# Activities.net
KiCad netlist of a schematic drawn in EAGLE
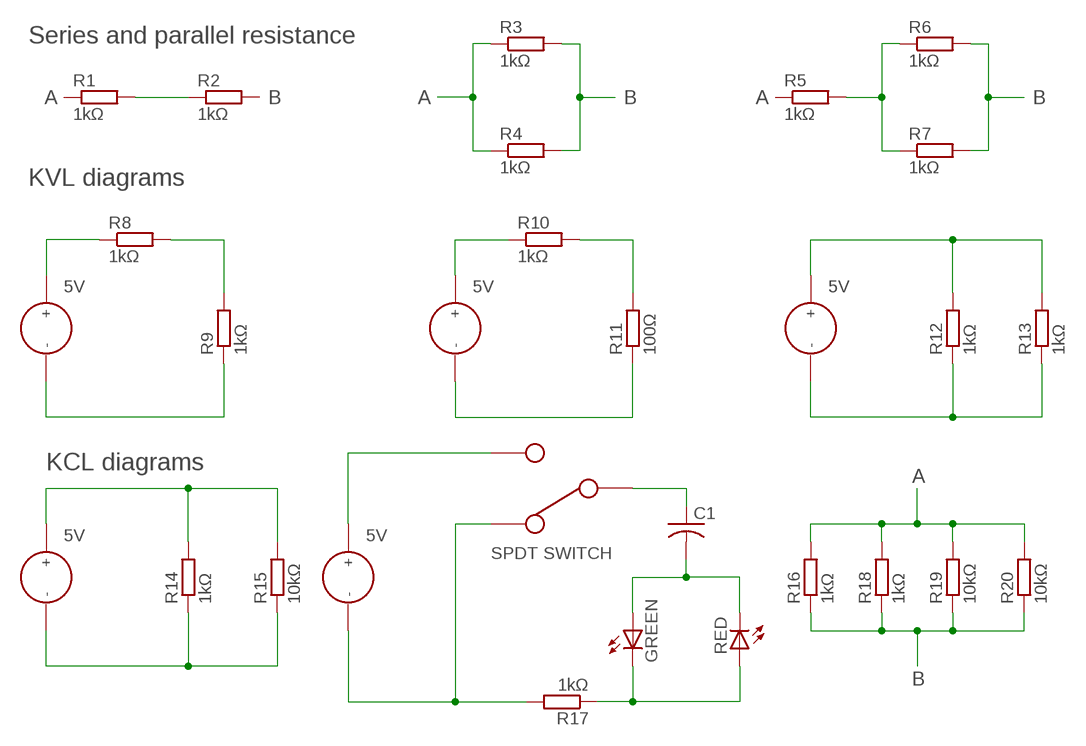
[diagram p0: schematic, sheet 1]

(export (version "E")
  (design (tool "Eeschema 10.0.6"))
  (components
    (comp (ref "C1")
      (value "C-US025-025X050")
      (footprint "eagle-import:C025-025X050")
      (libsource (lib "eagle-import") (part "C-US025-025X050"))
    )
    (comp (ref "GREEN")
      (value "LED3MM")
      (footprint "eagle-import:LED3MM")
      (libsource (lib "eagle-import") (part "LED3MM"))
    )
    (comp (ref "R1")
      (value "1kΩ")
      (footprint "eagle-import:0207_10")
      (libsource (lib "eagle-import") (part "R-EU_0207/10"))
    )
    (comp (ref "R2")
      (value "1kΩ")
      (footprint "eagle-import:0207_10")
      (libsource (lib "eagle-import") (part "R-EU_0207/10"))
    )
    (comp (ref "R3")
      (value "1kΩ")
      (footprint "eagle-import:0207_10")
      (libsource (lib "eagle-import") (part "R-EU_0207/10"))
    )
    (comp (ref "R4")
      (value "1kΩ")
      (footprint "eagle-import:0207_10")
      (libsource (lib "eagle-import") (part "R-EU_0207/10"))
    )
    (comp (ref "R5")
      (value "1kΩ")
      (footprint "eagle-import:0207_10")
      (libsource (lib "eagle-import") (part "R-EU_0207/10"))
    )
    (comp (ref "R6")
      (value "1kΩ")
      (footprint "eagle-import:0207_10")
      (libsource (lib "eagle-import") (part "R-EU_0207/10"))
    )
    (comp (ref "R7")
      (value "1kΩ")
      (footprint "eagle-import:0207_10")
      (libsource (lib "eagle-import") (part "R-EU_0207/10"))
    )
    (comp (ref "R8")
      (value "1kΩ")
      (footprint "eagle-import:0207_10")
      (libsource (lib "eagle-import") (part "R-EU_0207/10"))
    )
    (comp (ref "R9")
      (value "1kΩ")
      (footprint "eagle-import:0207_10")
      (libsource (lib "eagle-import") (part "R-EU_0207/10"))
    )
    (comp (ref "R10")
      (value "1kΩ")
      (footprint "eagle-import:0207_10")
      (libsource (lib "eagle-import") (part "R-EU_0207/10"))
    )
    (comp (ref "R11")
      (value "100Ω")
      (footprint "eagle-import:0207_10")
      (libsource (lib "eagle-import") (part "R-EU_0207/10"))
    )
    (comp (ref "R12")
      (value "1kΩ")
      (footprint "eagle-import:0207_10")
      (libsource (lib "eagle-import") (part "R-EU_0207/10"))
    )
    (comp (ref "R13")
      (value "1kΩ")
      (footprint "eagle-import:0207_10")
      (libsource (lib "eagle-import") (part "R-EU_0207/10"))
    )
    (comp (ref "R14")
      (value "1kΩ")
      (footprint "eagle-import:0207_10")
      (libsource (lib "eagle-import") (part "R-EU_0207/10"))
    )
    (comp (ref "R15")
      (value "10kΩ")
      (footprint "eagle-import:0207_10")
      (libsource (lib "eagle-import") (part "R-EU_0207/10"))
    )
    (comp (ref "R16")
      (value "1kΩ")
      (footprint "eagle-import:0207_10")
      (libsource (lib "eagle-import") (part "R-EU_0207/10"))
    )
    (comp (ref "R17")
      (value "1kΩ")
      (footprint "eagle-import:0207_10")
      (libsource (lib "eagle-import") (part "R-EU_0207/10"))
    )
    (comp (ref "R18")
      (value "1kΩ")
      (footprint "eagle-import:0207_10")
      (libsource (lib "eagle-import") (part "R-EU_0207/10"))
    )
    (comp (ref "R19")
      (value "10kΩ")
      (footprint "eagle-import:0207_10")
      (libsource (lib "eagle-import") (part "R-EU_0207/10"))
    )
    (comp (ref "R20")
      (value "10kΩ")
      (footprint "eagle-import:0207_10")
      (libsource (lib "eagle-import") (part "R-EU_0207/10"))
    )
    (comp (ref "RED")
      (value "LED3MM")
      (footprint "eagle-import:LED3MM")
      (libsource (lib "eagle-import") (part "LED3MM"))
    )
    (comp (ref "U$1")
      (value "SPDT")
      (footprint "eagle-import:SPDT")
      (libsource (lib "eagle-import") (part "SPDT"))
    )
    (comp (ref "V1")
      (value "5V")
      (footprint "eagle-import:VOLTAGE_SOURCE")
      (libsource (lib "eagle-import") (part "VOLTAGE_SOURCE"))
    )
    (comp (ref "V2")
      (value "5V")
      (footprint "eagle-import:VOLTAGE_SOURCE")
      (libsource (lib "eagle-import") (part "VOLTAGE_SOURCE"))
    )
    (comp (ref "V3")
      (value "5V")
      (footprint "eagle-import:VOLTAGE_SOURCE")
      (libsource (lib "eagle-import") (part "VOLTAGE_SOURCE"))
    )
    (comp (ref "V7")
      (value "5V")
      (footprint "eagle-import:VOLTAGE_SOURCE")
      (libsource (lib "eagle-import") (part "VOLTAGE_SOURCE"))
    )
    (comp (ref "V8")
      (value "5V")
      (footprint "eagle-import:VOLTAGE_SOURCE")
      (libsource (lib "eagle-import") (part "VOLTAGE_SOURCE"))
    )
  )
  (nets
    (net (code "1") (name "Net-(GREEN-C)") (class "Default")
      (node (ref "GREEN") (pin "K") (pinfunction "C_K") (pintype "passive"))
      (node (ref "R17") (pin "1") (pinfunction "1_1") (pintype "passive"))
      (node (ref "RED") (pin "A") (pinfunction "A_A") (pintype "passive"))
    )
    (net (code "2") (name "Net-(R1-Pad2)") (class "Default")
      (node (ref "R1") (pin "2") (pinfunction "2_2") (pintype "passive"))
      (node (ref "R2") (pin "1") (pinfunction "1_1") (pintype "passive"))
    )
    (net (code "3") (name "Net-(R3-Pad1)") (class "Default")
      (node (ref "R3") (pin "1") (pinfunction "1_1") (pintype "passive"))
      (node (ref "R4") (pin "1") (pinfunction "1_1") (pintype "passive"))
    )
    (net (code "4") (name "Net-(R3-Pad2)") (class "Default")
      (node (ref "R3") (pin "2") (pinfunction "2_2") (pintype "passive"))
      (node (ref "R4") (pin "2") (pinfunction "2_2") (pintype "passive"))
    )
    (net (code "5") (name "Net-(R5-Pad2)") (class "Default")
      (node (ref "R5") (pin "2") (pinfunction "2_2") (pintype "passive"))
      (node (ref "R6") (pin "1") (pinfunction "1_1") (pintype "passive"))
      (node (ref "R7") (pin "1") (pinfunction "1_1") (pintype "passive"))
    )
    (net (code "6") (name "Net-(R6-Pad2)") (class "Default")
      (node (ref "R6") (pin "2") (pinfunction "2_2") (pintype "passive"))
      (node (ref "R7") (pin "2") (pinfunction "2_2") (pintype "passive"))
    )
    (net (code "7") (name "Net-(R8-Pad2)") (class "Default")
      (node (ref "R8") (pin "2") (pinfunction "2_2") (pintype "passive"))
      (node (ref "R9") (pin "2") (pinfunction "2_2") (pintype "passive"))
    )
    (net (code "8") (name "Net-(R10-Pad2)") (class "Default")
      (node (ref "R10") (pin "2") (pinfunction "2_2") (pintype "passive"))
      (node (ref "R11") (pin "2") (pinfunction "2_2") (pintype "passive"))
    )
    (net (code "9") (name "Net-(R16-Pad1)") (class "Default")
      (node (ref "R16") (pin "1") (pinfunction "1_1") (pintype "passive"))
      (node (ref "R18") (pin "1") (pinfunction "1_1") (pintype "passive"))
      (node (ref "R19") (pin "1") (pinfunction "1_1") (pintype "passive"))
      (node (ref "R20") (pin "1") (pinfunction "1_1") (pintype "passive"))
    )
    (net (code "10") (name "Net-(R16-Pad2)") (class "Default")
      (node (ref "R16") (pin "2") (pinfunction "2_2") (pintype "passive"))
      (node (ref "R18") (pin "2") (pinfunction "2_2") (pintype "passive"))
      (node (ref "R19") (pin "2") (pinfunction "2_2") (pintype "passive"))
      (node (ref "R20") (pin "2") (pinfunction "2_2") (pintype "passive"))
    )
    (net (code "11") (name "Net-(RED-C)") (class "Default")
      (node (ref "C1") (pin "2") (pinfunction "2_2") (pintype "passive"))
      (node (ref "GREEN") (pin "A") (pinfunction "A_A") (pintype "passive"))
      (node (ref "RED") (pin "K") (pinfunction "C_K") (pintype "passive"))
    )
    (net (code "12") (name "Net-(U$1-A)") (class "Default")
      (node (ref "U$1") (pin "P$1") (pinfunction "A_P$1") (pintype "bidirectional"))
      (node (ref "V8") (pin "1") (pinfunction "+_1") (pintype "bidirectional"))
    )
    (net (code "13") (name "Net-(U$1-B)") (class "Default")
      (node (ref "R17") (pin "2") (pinfunction "2_2") (pintype "passive"))
      (node (ref "U$1") (pin "P$2") (pinfunction "B_P$2") (pintype "bidirectional"))
      (node (ref "V8") (pin "2") (pinfunction "-_2") (pintype "bidirectional"))
    )
    (net (code "14") (name "Net-(U$1-IN)") (class "Default")
      (node (ref "C1") (pin "1") (pinfunction "1_1") (pintype "passive"))
      (node (ref "U$1") (pin "P$3") (pinfunction "IN_P$3") (pintype "bidirectional"))
    )
    (net (code "15") (name "Net-(V1-+)") (class "Default")
      (node (ref "R8") (pin "1") (pinfunction "1_1") (pintype "passive"))
      (node (ref "V1") (pin "1") (pinfunction "+_1") (pintype "bidirectional"))
    )
    (net (code "16") (name "Net-(V1--)") (class "Default")
      (node (ref "R9") (pin "1") (pinfunction "1_1") (pintype "passive"))
      (node (ref "V1") (pin "2") (pinfunction "-_2") (pintype "bidirectional"))
    )
    (net (code "17") (name "Net-(V2-+)") (class "Default")
      (node (ref "R10") (pin "1") (pinfunction "1_1") (pintype "passive"))
      (node (ref "V2") (pin "1") (pinfunction "+_1") (pintype "bidirectional"))
    )
    (net (code "18") (name "Net-(V2--)") (class "Default")
      (node (ref "R11") (pin "1") (pinfunction "1_1") (pintype "passive"))
      (node (ref "V2") (pin "2") (pinfunction "-_2") (pintype "bidirectional"))
    )
    (net (code "19") (name "Net-(V3-+)") (class "Default")
      (node (ref "R12") (pin "2") (pinfunction "2_2") (pintype "passive"))
      (node (ref "R13") (pin "2") (pinfunction "2_2") (pintype "passive"))
      (node (ref "V3") (pin "1") (pinfunction "+_1") (pintype "bidirectional"))
    )
    (net (code "20") (name "Net-(V3--)") (class "Default")
      (node (ref "R12") (pin "1") (pinfunction "1_1") (pintype "passive"))
      (node (ref "R13") (pin "1") (pinfunction "1_1") (pintype "passive"))
      (node (ref "V3") (pin "2") (pinfunction "-_2") (pintype "bidirectional"))
    )
    (net (code "21") (name "Net-(V7-+)") (class "Default")
      (node (ref "R14") (pin "2") (pinfunction "2_2") (pintype "passive"))
      (node (ref "R15") (pin "2") (pinfunction "2_2") (pintype "passive"))
      (node (ref "V7") (pin "1") (pinfunction "+_1") (pintype "bidirectional"))
    )
    (net (code "22") (name "Net-(V7--)") (class "Default")
      (node (ref "R14") (pin "1") (pinfunction "1_1") (pintype "passive"))
      (node (ref "R15") (pin "1") (pinfunction "1_1") (pintype "passive"))
      (node (ref "V7") (pin "2") (pinfunction "-_2") (pintype "bidirectional"))
    )
    (net (code "23") (name "unconnected-(R1-Pad1)") (class "Default")
      (node (ref "R1") (pin "1") (pinfunction "1_1") (pintype "passive"))
    )
    (net (code "24") (name "unconnected-(R2-Pad2)") (class "Default")
      (node (ref "R2") (pin "2") (pinfunction "2_2") (pintype "passive"))
    )
    (net (code "25") (name "unconnected-(R5-Pad1)") (class "Default")
      (node (ref "R5") (pin "1") (pinfunction "1_1") (pintype "passive"))
    )
  )
)
